# ASCII_05_LMS7002M_RF1.net
KiCad netlist of a schematic drawn in Altium Designer
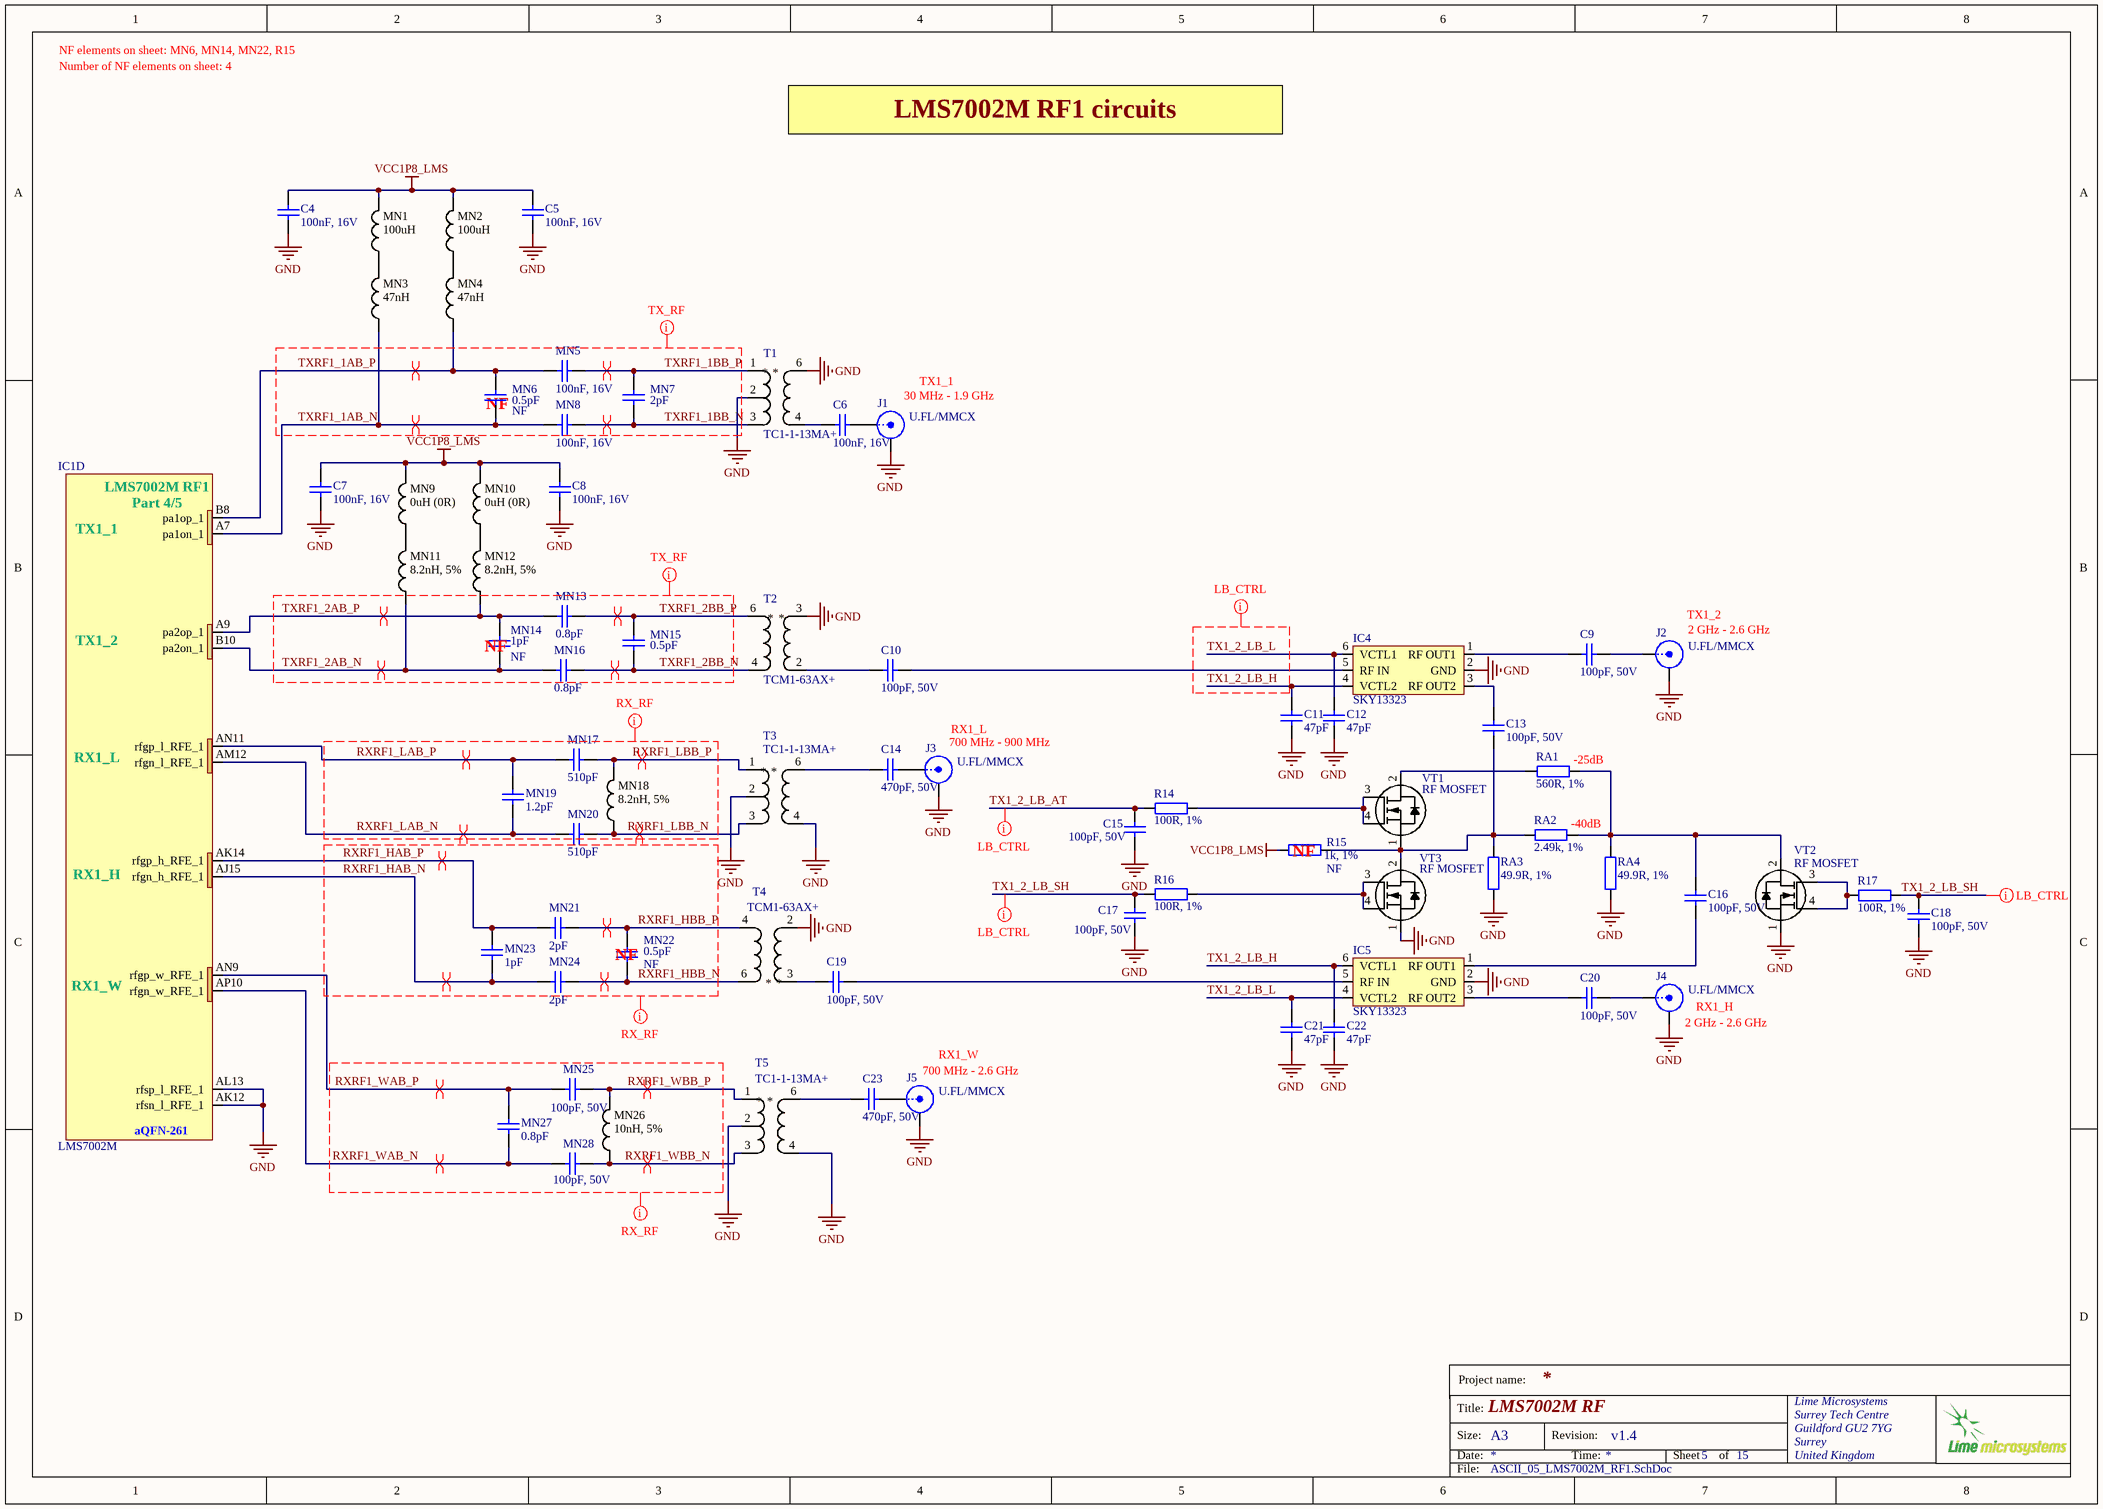
[diagram p0: ASCII_05_LMS7002M_RF1.SchDoc]

(export (version "E")
  (design (tool "Eeschema 10.0.6"))
  (components
    (comp (ref "C4")
      (value "100nF, 16V")
      (footprint "CAP0402")
      (fields
        (field (name "MANUFACTURER") "Murata Electronics")
        (field (name "TOLERANCE") "10 %")
        (field (name "MANUFACTURER PART NUMBER") "GRM155R71C104KA88D")
      )
      (libsource (lib "LimeMicroAltiumLib_schLib") (part "Cap_0402"))
    )
    (comp (ref "C5")
      (value "100nF, 16V")
      (footprint "CAP0402")
      (fields
        (field (name "MANUFACTURER") "Murata Electronics")
        (field (name "TOLERANCE") "10 %")
        (field (name "MANUFACTURER PART NUMBER") "GRM155R71C104KA88D")
      )
      (libsource (lib "LimeMicroAltiumLib_schLib") (part "Cap_0402"))
    )
    (comp (ref "C6")
      (value "100nF, 16V")
      (footprint "CAP0402")
      (fields
        (field (name "MANUFACTURER") "Murata Electronics")
        (field (name "TOLERANCE") "10 %")
        (field (name "MANUFACTURER PART NUMBER") "GRM155R71C104KA88D")
      )
      (libsource (lib "LimeMicroAltiumLib_schLib") (part "Cap_0402"))
    )
    (comp (ref "C7")
      (value "100nF, 16V")
      (footprint "CAP0402")
      (fields
        (field (name "MANUFACTURER") "Murata Electronics")
        (field (name "TOLERANCE") "10 %")
        (field (name "MANUFACTURER PART NUMBER") "GRM155R71C104KA88D")
      )
      (libsource (lib "LimeMicroAltiumLib_schLib") (part "Cap_0402"))
    )
    (comp (ref "C8")
      (value "100nF, 16V")
      (footprint "CAP0402")
      (fields
        (field (name "MANUFACTURER") "Murata Electronics")
        (field (name "TOLERANCE") "10 %")
        (field (name "MANUFACTURER PART NUMBER") "GRM155R71C104KA88D")
      )
      (libsource (lib "LimeMicroAltiumLib_schLib") (part "Cap_0402"))
    )
    (comp (ref "C9")
      (value "100pF, 50V")
      (footprint "CAP0402")
      (fields (field (name "TOLERANCE") "±5%") (field (name "MANUFACTURER") "Yageo"))
      (libsource (lib "LimeMicroAltiumLib_schLib") (part "Cap_0402"))
    )
    (comp (ref "C10")
      (value "100pF, 50V")
      (footprint "CAP0402")
      (fields (field (name "TOLERANCE") "±5%") (field (name "MANUFACTURER") "Yageo"))
      (libsource (lib "LimeMicroAltiumLib_schLib") (part "Cap_0402"))
    )
    (comp (ref "C11")
      (value "47pF")
      (footprint "CAP0402")
      (fields (field (name "TOLERANCE") "±1%") (field (name "MANUFACTURER") "TDK Corporation"))
      (libsource (lib "LimeMicroAltiumLib_schLib") (part "Cap_0402"))
    )
    (comp (ref "C12")
      (value "47pF")
      (footprint "CAP0402")
      (fields (field (name "TOLERANCE") "±1%") (field (name "MANUFACTURER") "TDK Corporation"))
      (libsource (lib "LimeMicroAltiumLib_schLib") (part "Cap_0402"))
    )
    (comp (ref "C13")
      (value "100pF, 50V")
      (footprint "CAP0402")
      (fields (field (name "TOLERANCE") "±5%") (field (name "MANUFACTURER") "Yageo"))
      (libsource (lib "LimeMicroAltiumLib_schLib") (part "Cap_0402"))
    )
    (comp (ref "C14")
      (value "470pF, 50V")
      (footprint "CAP0402")
      (fields
        (field (name "MANUFACTURER PART NUMBER") "C1005C0G1H471J050BA")
        (field (name "TOLERANCE") "±5%")
        (field (name "MANUFACTURER") "TDK Corporation")
      )
      (libsource (lib "LimeMicroAltiumLib_schLib") (part "Cap_0402"))
    )
    (comp (ref "C15")
      (value "100pF, 50V")
      (footprint "CAP0402")
      (fields (field (name "TOLERANCE") "±5%") (field (name "MANUFACTURER") "Yageo"))
      (libsource (lib "LimeMicroAltiumLib_schLib") (part "Cap_0402"))
    )
    (comp (ref "C16")
      (value "100pF, 50V")
      (footprint "CAP0402")
      (fields (field (name "TOLERANCE") "±5%") (field (name "MANUFACTURER") "Yageo"))
      (libsource (lib "LimeMicroAltiumLib_schLib") (part "Cap_0402"))
    )
    (comp (ref "C17")
      (value "100pF, 50V")
      (footprint "CAP0402")
      (fields (field (name "TOLERANCE") "±5%") (field (name "MANUFACTURER") "Yageo"))
      (libsource (lib "LimeMicroAltiumLib_schLib") (part "Cap_0402"))
    )
    (comp (ref "C18")
      (value "100pF, 50V")
      (footprint "CAP0402")
      (fields (field (name "TOLERANCE") "±5%") (field (name "MANUFACTURER") "Yageo"))
      (libsource (lib "LimeMicroAltiumLib_schLib") (part "Cap_0402"))
    )
    (comp (ref "C19")
      (value "100pF, 50V")
      (footprint "CAP0402")
      (fields (field (name "TOLERANCE") "±5%") (field (name "MANUFACTURER") "Yageo"))
      (libsource (lib "LimeMicroAltiumLib_schLib") (part "Cap_0402"))
    )
    (comp (ref "C20")
      (value "100pF, 50V")
      (footprint "CAP0402")
      (fields (field (name "TOLERANCE") "±5%") (field (name "MANUFACTURER") "Yageo"))
      (libsource (lib "LimeMicroAltiumLib_schLib") (part "Cap_0402"))
    )
    (comp (ref "C21")
      (value "47pF")
      (footprint "CAP0402")
      (fields (field (name "TOLERANCE") "±1%") (field (name "MANUFACTURER") "TDK Corporation"))
      (libsource (lib "LimeMicroAltiumLib_schLib") (part "Cap_0402"))
    )
    (comp (ref "C22")
      (value "47pF")
      (footprint "CAP0402")
      (fields (field (name "TOLERANCE") "±1%") (field (name "MANUFACTURER") "TDK Corporation"))
      (libsource (lib "LimeMicroAltiumLib_schLib") (part "Cap_0402"))
    )
    (comp (ref "C23")
      (value "470pF, 50V")
      (footprint "CAP0402")
      (fields
        (field (name "MANUFACTURER PART NUMBER") "C1005C0G1H471J050BA")
        (field (name "TOLERANCE") "±5%")
        (field (name "MANUFACTURER") "TDK Corporation")
      )
      (libsource (lib "LimeMicroAltiumLib_schLib") (part "Cap_0402"))
    )
    (comp (ref "IC1")
      (value "LMS7002M")
      (footprint "LMS7002M_v3")
      (fields (field (name "MANUFACTURER") "Lime Microsystems"))
      (libsource (lib "LimeMicroAltiumLib_schLib") (part "LMS7002M"))
    )
    (comp (ref "IC4")
      (value "SKY13323")
      (footprint "SKY13323-378LF")
      (description "SKY13323-378LF: 0.1-3.0 GHz GaAs SPDT Switch")
      (fields (field (name "MANUFACTURER") "Skyworks Solutions Inc."))
      (libsource (lib "LimeMicroAltiumLib_schLib") (part "SKY13323"))
    )
    (comp (ref "IC5")
      (value "SKY13323")
      (footprint "SKY13323-378LF")
      (description "SKY13323-378LF: 0.1-3.0 GHz GaAs SPDT Switch")
      (fields (field (name "MANUFACTURER") "Skyworks Solutions Inc."))
      (libsource (lib "LimeMicroAltiumLib_schLib") (part "SKY13323"))
    )
    (comp (ref "J1")
      (value "U.FL/MMCX")
      (footprint "MMCX_UFL_conn_u")
      (description "CONN UMC RCPT STR 50 OHM SMD")
      (fields (field (name "MANUFACTURER") "Molex, LLC"))
      (libsource (lib "LimeMicroAltiumLib_schLib") (part "RF_IF_connector"))
    )
    (comp (ref "J2")
      (value "U.FL/MMCX")
      (footprint "MMCX_UFL_conn_u")
      (description "CONN UMC RCPT STR 50 OHM SMD")
      (fields (field (name "MANUFACTURER") "Molex, LLC"))
      (libsource (lib "LimeMicroAltiumLib_schLib") (part "RF_IF_connector"))
    )
    (comp (ref "J3")
      (value "U.FL/MMCX")
      (footprint "MMCX_UFL_conn_u")
      (description "CONN UMC RCPT STR 50 OHM SMD")
      (fields (field (name "MANUFACTURER") "Molex, LLC"))
      (libsource (lib "LimeMicroAltiumLib_schLib") (part "RF_IF_connector"))
    )
    (comp (ref "J4")
      (value "U.FL/MMCX")
      (footprint "MMCX_UFL_conn_u")
      (description "CONN UMC RCPT STR 50 OHM SMD")
      (fields (field (name "MANUFACTURER") "Molex, LLC"))
      (libsource (lib "LimeMicroAltiumLib_schLib") (part "RF_IF_connector"))
    )
    (comp (ref "J5")
      (value "U.FL/MMCX")
      (footprint "MMCX_UFL_conn_u")
      (description "CONN UMC RCPT STR 50 OHM SMD")
      (fields (field (name "MANUFACTURER") "Molex, LLC"))
      (libsource (lib "LimeMicroAltiumLib_schLib") (part "RF_IF_connector"))
    )
    (comp (ref "MN1")
      (value "100uH")
      (footprint "RES0805")
      (fields
        (field (name "TOLERANCE") "±10%")
        (field (name "MANUFACTURER") "TDK Corporation")
        (field (name "MANUFACTURER PART NUMBER") "MLF2012C101KT000")
      )
      (libsource (lib "LimeMicroAltiumLib_schLib") (part "Inductor_0603"))
    )
    (comp (ref "MN2")
      (value "100uH")
      (footprint "RES0805")
      (fields
        (field (name "TOLERANCE") "±10%")
        (field (name "MANUFACTURER") "TDK Corporation")
        (field (name "MANUFACTURER PART NUMBER") "MLF2012C101KT000")
      )
      (libsource (lib "LimeMicroAltiumLib_schLib") (part "Inductor_0603"))
    )
    (comp (ref "MN3")
      (value "47nH")
      (footprint "RES0402")
      (fields
        (field (name "MANUFACTURER") "COILCRAFT")
        (field (name "MANUFACTURER PART NUMBER") "0402HP-47NXJLU")
      )
      (libsource (lib "LimeMicroAltiumLib_schLib") (part "Inductor_0603"))
    )
    (comp (ref "MN4")
      (value "47nH")
      (footprint "RES0402")
      (fields
        (field (name "MANUFACTURER") "COILCRAFT")
        (field (name "MANUFACTURER PART NUMBER") "0402HP-47NXJLU")
      )
      (libsource (lib "LimeMicroAltiumLib_schLib") (part "Inductor_0603"))
    )
    (comp (ref "MN5")
      (value "100nF, 16V")
      (footprint "CAP0402")
      (fields
        (field (name "MANUFACTURER") "Murata Electronics")
        (field (name "TOLERANCE") "10 %")
        (field (name "MANUFACTURER PART NUMBER") "GRM155R71C104KA88D")
      )
      (libsource (lib "LimeMicroAltiumLib_schLib") (part "Cap_0402"))
    )
    (comp (ref "MN6")
      (value "0.5pF")
      (footprint "CAP0402")
      (fields
        (field (name "ASSEMBLY INFO") "NF")
        (field (name "TOLERANCE") "±0.25pF")
        (field (name "MANUFACTURER") "Yageo")
      )
      (libsource (lib "LimeMicroAltiumLib_schLib") (part "Cap_0402"))
    )
    (comp (ref "MN7")
      (value "2pF")
      (footprint "CAP0402")
      (fields (field (name "MANUFACTURER PART NUMBER") "04025U2R0BAT2A") (field (name "MANUFACTURER") "AVX"))
      (libsource (lib "LimeMicroAltiumLib_schLib") (part "Cap_0402"))
    )
    (comp (ref "MN8")
      (value "100nF, 16V")
      (footprint "CAP0402")
      (fields
        (field (name "MANUFACTURER") "Murata Electronics")
        (field (name "TOLERANCE") "10 %")
        (field (name "MANUFACTURER PART NUMBER") "GRM155R71C104KA88D")
      )
      (libsource (lib "LimeMicroAltiumLib_schLib") (part "Cap_0402"))
    )
    (comp (ref "MN9")
      (value "0uH (0R)")
      (footprint "RES0805")
      (fields (field (name "MANUFACTURER") "BOURNS"))
      (libsource (lib "LimeMicroAltiumLib_schLib") (part "Inductor_0603"))
    )
    (comp (ref "MN10")
      (value "0uH (0R)")
      (footprint "RES0805")
      (fields (field (name "MANUFACTURER") "BOURNS"))
      (libsource (lib "LimeMicroAltiumLib_schLib") (part "Inductor_0603"))
    )
    (comp (ref "MN11")
      (value "8.2nH, 5%")
      (footprint "RES0402")
      (fields (field (name "MANUFACTURER") "COILCRAFT"))
      (libsource (lib "LimeMicroAltiumLib_schLib") (part "Inductor_0603"))
    )
    (comp (ref "MN12")
      (value "8.2nH, 5%")
      (footprint "RES0402")
      (fields (field (name "MANUFACTURER") "COILCRAFT"))
      (libsource (lib "LimeMicroAltiumLib_schLib") (part "Inductor_0603"))
    )
    (comp (ref "MN13")
      (value "0.8pF")
      (footprint "CAP0402")
      (fields
        (field (name "TOLERANCE") "±0.1pF")
        (field (name "MANUFACTURER") "Murata Electronics North America")
        (field (name "MANUFACTURER PART NUMBER") "GRM1555C1HR80BA01D")
      )
      (libsource (lib "LimeMicroAltiumLib_schLib") (part "Cap_0402"))
    )
    (comp (ref "MN14")
      (value "1pF")
      (footprint "CAP0402")
      (fields
        (field (name "ASSEMBLY INFO") "NF")
        (field (name "MANUFACTURER") "TDK Corporation")
        (field (name "TOLERANCE") "±0.1pF")
      )
      (libsource (lib "LimeMicroAltiumLib_schLib") (part "Cap_0402"))
    )
    (comp (ref "MN15")
      (value "0.5pF")
      (footprint "CAP0402")
      (fields (field (name "TOLERANCE") "±0.25pF") (field (name "MANUFACTURER") "Yageo"))
      (libsource (lib "LimeMicroAltiumLib_schLib") (part "Cap_0402"))
    )
    (comp (ref "MN16")
      (value "0.8pF")
      (footprint "CAP0402")
      (fields
        (field (name "TOLERANCE") "±0.1pF")
        (field (name "MANUFACTURER") "Murata Electronics North America")
        (field (name "MANUFACTURER PART NUMBER") "GRM1555C1HR80BA01D")
      )
      (libsource (lib "LimeMicroAltiumLib_schLib") (part "Cap_0402"))
    )
    (comp (ref "MN17")
      (value "510pF")
      (footprint "CAP0402")
      (fields
        (field (name "TOLERANCE") "±5%")
        (field (name "MANUFACTURER") "Murata Electronics North America")
        (field (name "MANUFACTURER PART NUMBER") "GRM1555C1H511JA01D")
      )
      (libsource (lib "LimeMicroAltiumLib_schLib") (part "Cap_0402"))
    )
    (comp (ref "MN18")
      (value "8.2nH, 5%")
      (footprint "RES0402")
      (fields (field (name "MANUFACTURER") "COILCRAFT"))
      (libsource (lib "LimeMicroAltiumLib_schLib") (part "Inductor_0603"))
    )
    (comp (ref "MN19")
      (value "1.2pF")
      (footprint "CAP0402")
      (fields
        (field (name "MANUFACTURER") "Murata Electronics North America")
        (field (name "MANUFACTURER PART NUMBER") "GRM1555C1H1R2CA01D")
        (field (name "TOLERANCE") "±0.25pF")
      )
      (libsource (lib "LimeMicroAltiumLib_schLib") (part "Cap_0402"))
    )
    (comp (ref "MN20")
      (value "510pF")
      (footprint "CAP0402")
      (fields
        (field (name "TOLERANCE") "±5%")
        (field (name "MANUFACTURER") "Murata Electronics North America")
        (field (name "MANUFACTURER PART NUMBER") "GRM1555C1H511JA01D")
      )
      (libsource (lib "LimeMicroAltiumLib_schLib") (part "Cap_0402"))
    )
    (comp (ref "MN21")
      (value "2pF")
      (footprint "CAP0402")
      (fields (field (name "MANUFACTURER PART NUMBER") "04025U2R0BAT2A") (field (name "MANUFACTURER") "AVX"))
      (libsource (lib "LimeMicroAltiumLib_schLib") (part "Cap_0402"))
    )
    (comp (ref "MN22")
      (value "0.5pF")
      (footprint "CAP0402")
      (fields
        (field (name "ASSEMBLY INFO") "NF")
        (field (name "TOLERANCE") "±0.25pF")
        (field (name "MANUFACTURER") "Yageo")
      )
      (libsource (lib "LimeMicroAltiumLib_schLib") (part "Cap_0402"))
    )
    (comp (ref "MN23")
      (value "1pF")
      (footprint "CAP0402")
      (fields (field (name "MANUFACTURER") "TDK Corporation") (field (name "TOLERANCE") "±0.1pF"))
      (libsource (lib "LimeMicroAltiumLib_schLib") (part "Cap_0402"))
    )
    (comp (ref "MN24")
      (value "2pF")
      (footprint "CAP0402")
      (fields (field (name "MANUFACTURER PART NUMBER") "04025U2R0BAT2A") (field (name "MANUFACTURER") "AVX"))
      (libsource (lib "LimeMicroAltiumLib_schLib") (part "Cap_0402"))
    )
    (comp (ref "MN25")
      (value "100pF, 50V")
      (footprint "CAP0402")
      (fields (field (name "TOLERANCE") "±5%") (field (name "MANUFACTURER") "Yageo"))
      (libsource (lib "LimeMicroAltiumLib_schLib") (part "Cap_0402"))
    )
    (comp (ref "MN26")
      (value "10nH, 5%")
      (footprint "RES0402")
      (fields (field (name "MANUFACTURER") "COILCRAFT"))
      (libsource (lib "LimeMicroAltiumLib_schLib") (part "Inductor_0603"))
    )
    (comp (ref "MN27")
      (value "0.8pF")
      (footprint "CAP0402")
      (fields
        (field (name "TOLERANCE") "±0.1pF")
        (field (name "MANUFACTURER") "Murata Electronics North America")
        (field (name "MANUFACTURER PART NUMBER") "GRM1555C1HR80BA01D")
      )
      (libsource (lib "LimeMicroAltiumLib_schLib") (part "Cap_0402"))
    )
    (comp (ref "MN28")
      (value "100pF, 50V")
      (footprint "CAP0402")
      (fields (field (name "TOLERANCE") "±5%") (field (name "MANUFACTURER") "Yageo"))
      (libsource (lib "LimeMicroAltiumLib_schLib") (part "Cap_0402"))
    )
    (comp (ref "R14")
      (value "100R, 1%")
      (footprint "RES0402")
      (fields (field (name "TOLERANCE") "±1%") (field (name "MANUFACTURER") "Stackpole Electronics Inc."))
      (libsource (lib "LimeFPGAboard_schLib") (part "Res_0402"))
    )
    (comp (ref "R15")
      (value "1k, 1%")
      (footprint "RES0402")
      (fields
        (field (name "ASSEMBLY INFO") "NF")
        (field (name "MANUFACTURER") "Stackpole Electronics Inc")
        (field (name "TOLERANCE") "±1%")
      )
      (libsource (lib "LimeMicroAltiumLib_schLib") (part "Res_0402"))
    )
    (comp (ref "R16")
      (value "100R, 1%")
      (footprint "RES0402")
      (fields (field (name "TOLERANCE") "±1%") (field (name "MANUFACTURER") "Stackpole Electronics Inc."))
      (libsource (lib "LimeFPGAboard_schLib") (part "Res_0402"))
    )
    (comp (ref "R17")
      (value "100R, 1%")
      (footprint "RES0402")
      (fields (field (name "TOLERANCE") "±1%") (field (name "MANUFACTURER") "Stackpole Electronics Inc."))
      (libsource (lib "LimeFPGAboard_schLib") (part "Res_0402"))
    )
    (comp (ref "RA1")
      (value "560R, 1%")
      (footprint "RES0402")
      (fields
        (field (name "MANUFACTURER PART NUMBER") "CRCW0402560RFKED")
        (field (name "TOLERANCE") "±1%")
        (field (name "MANUFACTURER") "Vishay Dale")
      )
      (libsource (lib "LimeMicroAltiumLib_schLib") (part "Res_0402"))
    )
    (comp (ref "RA2")
      (value "2.49k, 1%")
      (footprint "RES0402")
      (fields
        (field (name "TOLERANCE") "±1%")
        (field (name "MANUFACTURER PART NUMBER") "RC0402FR-072K49L")
        (field (name "MANUFACTURER") "Yageo")
      )
      (libsource (lib "LimeMicroAltiumLib_schLib") (part "Res_0402"))
    )
    (comp (ref "RA3")
      (value "49.9R, 1%")
      (footprint "RES0402")
      (fields
        (field (name "TOLERANCE") "±1%")
        (field (name "MANUFACTURER") "Samsung Electro-Mechanics America, Inc.")
        (field (name "MANUFACTURER PART NUMBER") "RC1005F49R9CS")
      )
      (libsource (lib "LimeMicroAltiumLib_schLib") (part "Res_0402"))
    )
    (comp (ref "RA4")
      (value "49.9R, 1%")
      (footprint "RES0402")
      (fields
        (field (name "TOLERANCE") "±1%")
        (field (name "MANUFACTURER") "Samsung Electro-Mechanics America, Inc.")
        (field (name "MANUFACTURER PART NUMBER") "RC1005F49R9CS")
      )
      (libsource (lib "LimeMicroAltiumLib_schLib") (part "Res_0402"))
    )
    (comp (ref "T1")
      (value "TC1-1-13MA+")
      (footprint "TC1-1-13MA+_v2")
      (fields (field (name "MANUFACTURER") "Mini-Circuits"))
      (libsource (lib "LimeMicroAltiumLib_schLib") (part "Balun"))
    )
    (comp (ref "T2")
      (value "TCM1-63AX+")
      (footprint "TCM1-63AX+_v2")
      (fields (field (name "MANUFACTURER") "Mini-circuits"))
      (libsource (lib "") (part "Balun_v2_1"))
    )
    (comp (ref "T3")
      (value "TC1-1-13MA+")
      (footprint "TC1-1-13MA+_v2")
      (fields (field (name "MANUFACTURER") "Mini-Circuits"))
      (libsource (lib "LimeMicroAltiumLib_schLib") (part "Balun"))
    )
    (comp (ref "T4")
      (value "TCM1-63AX+")
      (footprint "TCM1-63AX+_v2")
      (fields (field (name "MANUFACTURER") "Mini-circuits"))
      (libsource (lib "LimeMicroAltiumLib_schLib") (part "Balun_v2"))
    )
    (comp (ref "T5")
      (value "TC1-1-13MA+")
      (footprint "TC1-1-13MA+_v2")
      (fields (field (name "MANUFACTURER") "Mini-Circuits"))
      (libsource (lib "LimeMicroAltiumLib_schLib") (part "Balun"))
    )
    (comp (ref "VT1")
      (value "RF MOSFET")
      (footprint "BF1105R_SOT143R4")
      (fields (field (name "MANUFACTURER") "NXP Semiconductors"))
      (libsource (lib "LimeMicroAltiumLib_schLib") (part "BF1105R,215"))
    )
    (comp (ref "VT2")
      (value "RF MOSFET")
      (footprint "BF1105R_SOT143R4")
      (fields (field (name "MANUFACTURER") "NXP Semiconductors"))
      (libsource (lib "LimeMicroAltiumLib_schLib") (part "BF1105R,215"))
    )
    (comp (ref "VT3")
      (value "RF MOSFET")
      (footprint "BF1105R_SOT143R4")
      (fields (field (name "MANUFACTURER") "NXP Semiconductors"))
      (libsource (lib "LimeMicroAltiumLib_schLib") (part "BF1105R,215"))
    )
  )
  (nets
    (net (code "1") (name "/RXRF1_HAB_N") (class "Default")
      (node (ref "IC1") (pin "AJ15") (pinfunction "rfgn_h_RFE_1_AJ15") (pintype "passive"))
      (node (ref "MN23") (pin "1") (pinfunction "1_1") (pintype "passive"))
      (node (ref "MN24") (pin "2") (pinfunction "2_2") (pintype "passive"))
    )
    (net (code "2") (name "/RXRF1_HAB_P") (class "Default")
      (node (ref "IC1") (pin "AK14") (pinfunction "rfgp_h_RFE_1_AK14") (pintype "passive"))
      (node (ref "MN21") (pin "2") (pinfunction "2_2") (pintype "passive"))
      (node (ref "MN23") (pin "2") (pinfunction "2_2") (pintype "passive"))
    )
    (net (code "3") (name "/RXRF1_HBB_N") (class "Default")
      (node (ref "MN22") (pin "1") (pinfunction "1_1") (pintype "passive"))
      (node (ref "MN24") (pin "1") (pinfunction "1_1") (pintype "passive"))
      (node (ref "T4") (pin "6") (pinfunction "6_6") (pintype "passive"))
    )
    (net (code "4") (name "/RXRF1_HBB_P") (class "Default")
      (node (ref "MN21") (pin "1") (pinfunction "1_1") (pintype "passive"))
      (node (ref "MN22") (pin "2") (pinfunction "2_2") (pintype "passive"))
      (node (ref "T4") (pin "4") (pinfunction "4_4") (pintype "passive"))
    )
    (net (code "5") (name "/RXRF1_LAB_N") (class "Default")
      (node (ref "IC1") (pin "AM12") (pinfunction "rfgn_l_RFE_1_AM12") (pintype "passive"))
      (node (ref "MN19") (pin "1") (pinfunction "1_1") (pintype "passive"))
      (node (ref "MN20") (pin "2") (pinfunction "2_2") (pintype "passive"))
    )
    (net (code "6") (name "/RXRF1_LAB_P") (class "Default")
      (node (ref "IC1") (pin "AN11") (pinfunction "rfgp_l_RFE_1_AN11") (pintype "passive"))
      (node (ref "MN17") (pin "2") (pinfunction "2_2") (pintype "passive"))
      (node (ref "MN19") (pin "2") (pinfunction "2_2") (pintype "passive"))
    )
    (net (code "7") (name "/RXRF1_LBB_N") (class "Default")
      (node (ref "MN18") (pin "1") (pinfunction "1_1") (pintype "passive"))
      (node (ref "MN20") (pin "1") (pinfunction "1_1") (pintype "passive"))
      (node (ref "T3") (pin "3") (pinfunction "3_3") (pintype "passive"))
    )
    (net (code "8") (name "/RXRF1_LBB_P") (class "Default")
      (node (ref "MN17") (pin "1") (pinfunction "1_1") (pintype "passive"))
      (node (ref "MN18") (pin "2") (pinfunction "2_2") (pintype "passive"))
      (node (ref "T3") (pin "1") (pinfunction "1_1") (pintype "passive"))
    )
    (net (code "9") (name "/RXRF1_WAB_N") (class "Default")
      (node (ref "IC1") (pin "AP10") (pinfunction "rfgn_w_RFE_1_AP10") (pintype "passive"))
      (node (ref "MN27") (pin "2") (pinfunction "2_2") (pintype "passive"))
      (node (ref "MN28") (pin "2") (pinfunction "2_2") (pintype "passive"))
    )
    (net (code "10") (name "/RXRF1_WAB_P") (class "Default")
      (node (ref "IC1") (pin "AN9") (pinfunction "rfgp_w_RFE_1_AN9") (pintype "passive"))
      (node (ref "MN25") (pin "2") (pinfunction "2_2") (pintype "passive"))
      (node (ref "MN27") (pin "1") (pinfunction "1_1") (pintype "passive"))
    )
    (net (code "11") (name "/RXRF1_WBB_N") (class "Default")
      (node (ref "MN26") (pin "1") (pinfunction "1_1") (pintype "passive"))
      (node (ref "MN28") (pin "1") (pinfunction "1_1") (pintype "passive"))
      (node (ref "T5") (pin "3") (pinfunction "3_3") (pintype "passive"))
    )
    (net (code "12") (name "/RXRF1_WBB_P") (class "Default")
      (node (ref "MN25") (pin "1") (pinfunction "1_1") (pintype "passive"))
      (node (ref "MN26") (pin "2") (pinfunction "2_2") (pintype "passive"))
      (node (ref "T5") (pin "1") (pinfunction "1_1") (pintype "passive"))
    )
    (net (code "13") (name "/TX1_2_LB_AT") (class "Default")
      (node (ref "C15") (pin "1") (pinfunction "1_1") (pintype "passive"))
      (node (ref "R14") (pin "2") (pinfunction "2_2") (pintype "passive"))
    )
    (net (code "14") (name "/TX1_2_LB_H") (class "Default")
      (node (ref "C11") (pin "2") (pinfunction "2_2") (pintype "passive"))
      (node (ref "C22") (pin "2") (pinfunction "2_2") (pintype "passive"))
      (node (ref "IC4") (pin "4") (pinfunction "VCTL2_4") (pintype "input"))
      (node (ref "IC5") (pin "6") (pinfunction "VCTL1_6") (pintype "input"))
    )
    (net (code "15") (name "/TX1_2_LB_L") (class "Default")
      (node (ref "C12") (pin "2") (pinfunction "2_2") (pintype "passive"))
      (node (ref "C21") (pin "2") (pinfunction "2_2") (pintype "passive"))
      (node (ref "IC4") (pin "6") (pinfunction "VCTL1_6") (pintype "input"))
      (node (ref "IC5") (pin "4") (pinfunction "VCTL2_4") (pintype "input"))
    )
    (net (code "16") (name "/TX1_2_LB_SH") (class "Default")
      (node (ref "C17") (pin "1") (pinfunction "1_1") (pintype "passive"))
      (node (ref "C18") (pin "1") (pinfunction "1_1") (pintype "passive"))
      (node (ref "R16") (pin "2") (pinfunction "2_2") (pintype "passive"))
      (node (ref "R17") (pin "1") (pinfunction "1_1") (pintype "passive"))
    )
    (net (code "17") (name "/TXRF1_1AB_N") (class "Default")
      (node (ref "IC1") (pin "A7") (pinfunction "pa1on_1_A7") (pintype "passive"))
      (node (ref "MN3") (pin "1") (pinfunction "1_1") (pintype "passive"))
      (node (ref "MN6") (pin "1") (pinfunction "1_1") (pintype "passive"))
      (node (ref "MN8") (pin "1") (pinfunction "1_1") (pintype "passive"))
    )
    (net (code "18") (name "/TXRF1_1AB_P") (class "Default")
      (node (ref "IC1") (pin "B8") (pinfunction "pa1op_1_B8") (pintype "passive"))
      (node (ref "MN4") (pin "1") (pinfunction "1_1") (pintype "passive"))
      (node (ref "MN5") (pin "2") (pinfunction "2_2") (pintype "passive"))
      (node (ref "MN6") (pin "2") (pinfunction "2_2") (pintype "passive"))
    )
    (net (code "19") (name "/TXRF1_1BB_N") (class "Default")
      (node (ref "MN7") (pin "1") (pinfunction "1_1") (pintype "passive"))
      (node (ref "MN8") (pin "2") (pinfunction "2_2") (pintype "passive"))
      (node (ref "T1") (pin "3") (pinfunction "3_3") (pintype "passive"))
    )
    (net (code "20") (name "/TXRF1_1BB_P") (class "Default")
      (node (ref "MN5") (pin "1") (pinfunction "1_1") (pintype "passive"))
      (node (ref "MN7") (pin "2") (pinfunction "2_2") (pintype "passive"))
      (node (ref "T1") (pin "1") (pinfunction "1_1") (pintype "passive"))
    )
    (net (code "21") (name "/TXRF1_2AB_N") (class "Default")
      (node (ref "IC1") (pin "B10") (pinfunction "pa2on_1_B10") (pintype "passive"))
      (node (ref "MN11") (pin "1") (pinfunction "1_1") (pintype "passive"))
      (node (ref "MN14") (pin "2") (pinfunction "2_2") (pintype "passive"))
      (node (ref "MN16") (pin "2") (pinfunction "2_2") (pintype "passive"))
    )
    (net (code "22") (name "/TXRF1_2AB_P") (class "Default")
      (node (ref "IC1") (pin "A9") (pinfunction "pa2op_1_A9") (pintype "passive"))
      (node (ref "MN12") (pin "1") (pinfunction "1_1") (pintype "passive"))
      (node (ref "MN13") (pin "2") (pinfunction "2_2") (pintype "passive"))
      (node (ref "MN14") (pin "1") (pinfunction "1_1") (pintype "passive"))
    )
    (net (code "23") (name "/TXRF1_2BB_N") (class "Default")
      (node (ref "MN15") (pin "1") (pinfunction "1_1") (pintype "passive"))
      (node (ref "MN16") (pin "1") (pinfunction "1_1") (pintype "passive"))
      (node (ref "T2") (pin "4") (pinfunction "4_4") (pintype "passive"))
    )
    (net (code "24") (name "/TXRF1_2BB_P") (class "Default")
      (node (ref "MN13") (pin "1") (pinfunction "1_1") (pintype "passive"))
      (node (ref "MN15") (pin "2") (pinfunction "2_2") (pintype "passive"))
      (node (ref "T2") (pin "6") (pinfunction "6_6") (pintype "passive"))
    )
    (net (code "25") (name "GND") (class "Default")
      (node (ref "C11") (pin "1") (pinfunction "1_1") (pintype "passive"))
      (node (ref "C12") (pin "1") (pinfunction "1_1") (pintype "passive"))
      (node (ref "C15") (pin "2") (pinfunction "2_2") (pintype "passive"))
      (node (ref "C17") (pin "2") (pinfunction "2_2") (pintype "passive"))
      (node (ref "C18") (pin "2") (pinfunction "2_2") (pintype "passive"))
      (node (ref "C21") (pin "1") (pinfunction "1_1") (pintype "passive"))
      (node (ref "C22") (pin "1") (pinfunction "1_1") (pintype "passive"))
      (node (ref "C4") (pin "1") (pinfunction "1_1") (pintype "passive"))
      (node (ref "C5") (pin "1") (pinfunction "1_1") (pintype "passive"))
      (node (ref "C7") (pin "1") (pinfunction "1_1") (pintype "passive"))
      (node (ref "C8") (pin "1") (pinfunction "1_1") (pintype "passive"))
      (node (ref "IC1") (pin "AK12") (pinfunction "rfsn_l_RFE_1_AK12") (pintype "passive"))
      (node (ref "IC1") (pin "AL13") (pinfunction "rfsp_l_RFE_1_AL13") (pintype "passive"))
      (node (ref "IC4") (pin "2") (pinfunction "GND_2") (pintype "passive"))
      (node (ref "IC5") (pin "2") (pinfunction "GND_2") (pintype "passive"))
      (node (ref "J1") (pin "2") (pinfunction "Y_2") (pintype "passive"))
      (node (ref "J2") (pin "2") (pinfunction "Y_2") (pintype "passive"))
      (node (ref "J3") (pin "2") (pinfunction "Y_2") (pintype "passive"))
      (node (ref "J4") (pin "2") (pinfunction "Y_2") (pintype "passive"))
      (node (ref "J5") (pin "2") (pinfunction "Y_2") (pintype "passive"))
      (node (ref "RA3") (pin "1") (pinfunction "1_1") (pintype "passive"))
      (node (ref "RA4") (pin "1") (pinfunction "1_1") (pintype "passive"))
      (node (ref "T1") (pin "2") (pinfunction "2_2") (pintype "passive"))
      (node (ref "T1") (pin "6") (pinfunction "6_6") (pintype "passive"))
      (node (ref "T2") (pin "3") (pinfunction "3_3") (pintype "passive"))
      (node (ref "T3") (pin "2") (pinfunction "2_2") (pintype "passive"))
      (node (ref "T3") (pin "4") (pinfunction "4_4") (pintype "passive"))
      (node (ref "T4") (pin "2") (pinfunction "2_2") (pintype "passive"))
      (node (ref "T5") (pin "2") (pinfunction "2_2") (pintype "passive"))
      (node (ref "T5") (pin "4") (pinfunction "4_4") (pintype "passive"))
      (node (ref "VT2") (pin "1") (pinfunction "S_1") (pintype "passive"))
      (node (ref "VT3") (pin "1") (pinfunction "S_1") (pintype "passive"))
    )
    (net (code "26") (name "Net-(C6-Pad2)") (class "Default")
      (node (ref "C6") (pin "2") (pinfunction "2_2") (pintype "passive"))
      (node (ref "T1") (pin "4") (pinfunction "4_4") (pintype "passive"))
    )
    (net (code "27") (name "Net-(C10-Pad2)") (class "Default")
      (node (ref "C10") (pin "2") (pinfunction "2_2") (pintype "passive"))
      (node (ref "T2") (pin "2") (pinfunction "2_2") (pintype "passive"))
    )
    (net (code "28") (name "Net-(C14-Pad2)") (class "Default")
      (node (ref "C14") (pin "2") (pinfunction "2_2") (pintype "passive"))
      (node (ref "T3") (pin "6") (pinfunction "6_6") (pintype "passive"))
    )
    (net (code "29") (name "Net-(C19-Pad2)") (class "Default")
      (node (ref "C19") (pin "2") (pinfunction "2_2") (pintype "passive"))
      (node (ref "T4") (pin "3") (pinfunction "3_3") (pintype "passive"))
    )
    (net (code "30") (name "Net-(C23-Pad2)") (class "Default")
      (node (ref "C23") (pin "2") (pinfunction "2_2") (pintype "passive"))
      (node (ref "T5") (pin "6") (pinfunction "6_6") (pintype "passive"))
    )
    (net (code "31") (name "Net-(IC4-RF_IN)") (class "Default")
      (node (ref "C10") (pin "1") (pinfunction "1_1") (pintype "passive"))
      (node (ref "IC4") (pin "5") (pinfunction "RF_IN_5") (pintype "input"))
    )
    (net (code "32") (name "Net-(IC4-RF_OUT1)") (class "Default")
      (node (ref "C9") (pin "2") (pinfunction "2_2") (pintype "passive"))
      (node (ref "IC4") (pin "1") (pinfunction "RF_OUT1_1") (pintype "output"))
    )
    (net (code "33") (name "Net-(IC4-RF_OUT2)") (class "Default")
      (node (ref "C13") (pin "1") (pinfunction "1_1") (pintype "passive"))
      (node (ref "IC4") (pin "3") (pinfunction "RF_OUT2_3") (pintype "output"))
    )
    (net (code "34") (name "Net-(IC5-RF_IN)") (class "Default")
      (node (ref "C19") (pin "1") (pinfunction "1_1") (pintype "passive"))
      (node (ref "IC5") (pin "5") (pinfunction "RF_IN_5") (pintype "input"))
    )
    (net (code "35") (name "Net-(IC5-RF_OUT1)") (class "Default")
      (node (ref "C16") (pin "2") (pinfunction "2_2") (pintype "passive"))
      (node (ref "IC5") (pin "1") (pinfunction "RF_OUT1_1") (pintype "output"))
    )
    (net (code "36") (name "Net-(IC5-RF_OUT2)") (class "Default")
      (node (ref "C20") (pin "2") (pinfunction "2_2") (pintype "passive"))
      (node (ref "IC5") (pin "3") (pinfunction "RF_OUT2_3") (pintype "output"))
    )
    (net (code "37") (name "Net-(J1-X)") (class "Default")
      (node (ref "C6") (pin "1") (pinfunction "1_1") (pintype "passive"))
      (node (ref "J1") (pin "1") (pinfunction "X_1") (pintype "passive"))
    )
    (net (code "38") (name "Net-(J2-X)") (class "Default")
      (node (ref "C9") (pin "1") (pinfunction "1_1") (pintype "passive"))
      (node (ref "J2") (pin "1") (pinfunction "X_1") (pintype "passive"))
    )
    (net (code "39") (name "Net-(J3-X)") (class "Default")
      (node (ref "C14") (pin "1") (pinfunction "1_1") (pintype "passive"))
      (node (ref "J3") (pin "1") (pinfunction "X_1") (pintype "passive"))
    )
    (net (code "40") (name "Net-(J4-X)") (class "Default")
      (node (ref "C20") (pin "1") (pinfunction "1_1") (pintype "passive"))
      (node (ref "J4") (pin "1") (pinfunction "X_1") (pintype "passive"))
    )
    (net (code "41") (name "Net-(J5-X)") (class "Default")
      (node (ref "C23") (pin "1") (pinfunction "1_1") (pintype "passive"))
      (node (ref "J5") (pin "1") (pinfunction "X_1") (pintype "passive"))
    )
    (net (code "42") (name "Net-(MN1-Pad1)") (class "Default")
      (node (ref "MN1") (pin "1") (pinfunction "1_1") (pintype "passive"))
      (node (ref "MN3") (pin "2") (pinfunction "2_2") (pintype "passive"))
    )
    (net (code "43") (name "Net-(MN2-Pad1)") (class "Default")
      (node (ref "MN2") (pin "1") (pinfunction "1_1") (pintype "passive"))
      (node (ref "MN4") (pin "2") (pinfunction "2_2") (pintype "passive"))
    )
    (net (code "44") (name "Net-(MN10-Pad1)") (class "Default")
      (node (ref "MN10") (pin "1") (pinfunction "1_1") (pintype "passive"))
      (node (ref "MN12") (pin "2") (pinfunction "2_2") (pintype "passive"))
    )
    (net (code "45") (name "Net-(MN11-Pad2)") (class "Default")
      (node (ref "MN11") (pin "2") (pinfunction "2_2") (pintype "passive"))
      (node (ref "MN9") (pin "1") (pinfunction "1_1") (pintype "passive"))
    )
    (net (code "46") (name "Net-(VT1-D)") (class "Default")
      (node (ref "RA1") (pin "2") (pinfunction "2_2") (pintype "passive"))
      (node (ref "VT1") (pin "2") (pinfunction "D_2") (pintype "passive"))
    )
    (net (code "47") (name "Net-(VT1-G1)") (class "Default")
      (node (ref "R14") (pin "1") (pinfunction "1_1") (pintype "passive"))
      (node (ref "VT1") (pin "3") (pinfunction "G2_3") (pintype "passive"))
      (node (ref "VT1") (pin "4") (pinfunction "G1_4") (pintype "passive"))
    )
    (net (code "48") (name "Net-(VT1-S)") (class "Default")
      (node (ref "C13") (pin "2") (pinfunction "2_2") (pintype "passive"))
      (node (ref "R15") (pin "1") (pinfunction "1_1") (pintype "passive"))
      (node (ref "RA2") (pin "1") (pinfunction "1_1") (pintype "passive"))
      (node (ref "RA3") (pin "2") (pinfunction "2_2") (pintype "passive"))
      (node (ref "VT1") (pin "1") (pinfunction "S_1") (pintype "passive"))
      (node (ref "VT3") (pin "2") (pinfunction "D_2") (pintype "passive"))
    )
    (net (code "49") (name "Net-(VT2-D)") (class "Default")
      (node (ref "C16") (pin "1") (pinfunction "1_1") (pintype "passive"))
      (node (ref "RA1") (pin "1") (pinfunction "1_1") (pintype "passive"))
      (node (ref "RA2") (pin "2") (pinfunction "2_2") (pintype "passive"))
      (node (ref "RA4") (pin "2") (pinfunction "2_2") (pintype "passive"))
      (node (ref "VT2") (pin "2") (pinfunction "D_2") (pintype "passive"))
    )
    (net (code "50") (name "Net-(VT2-G1)") (class "Default")
      (node (ref "R17") (pin "2") (pinfunction "2_2") (pintype "passive"))
      (node (ref "VT2") (pin "3") (pinfunction "G2_3") (pintype "passive"))
      (node (ref "VT2") (pin "4") (pinfunction "G1_4") (pintype "passive"))
    )
    (net (code "51") (name "Net-(VT3-G1)") (class "Default")
      (node (ref "R16") (pin "1") (pinfunction "1_1") (pintype "passive"))
      (node (ref "VT3") (pin "3") (pinfunction "G2_3") (pintype "passive"))
      (node (ref "VT3") (pin "4") (pinfunction "G1_4") (pintype "passive"))
    )
    (net (code "52") (name "VCC1P8_LMS") (class "Default")
      (node (ref "C4") (pin "2") (pinfunction "2_2") (pintype "passive"))
      (node (ref "C5") (pin "2") (pinfunction "2_2") (pintype "passive"))
      (node (ref "C7") (pin "2") (pinfunction "2_2") (pintype "passive"))
      (node (ref "C8") (pin "2") (pinfunction "2_2") (pintype "passive"))
      (node (ref "MN1") (pin "2") (pinfunction "2_2") (pintype "passive"))
      (node (ref "MN10") (pin "2") (pinfunction "2_2") (pintype "passive"))
      (node (ref "MN2") (pin "2") (pinfunction "2_2") (pintype "passive"))
      (node (ref "MN9") (pin "2") (pinfunction "2_2") (pintype "passive"))
      (node (ref "R15") (pin "2") (pinfunction "2_2") (pintype "passive"))
    )
  )
)
